# CPU.net
KiCad netlist of a schematic drawn in Altium Designer
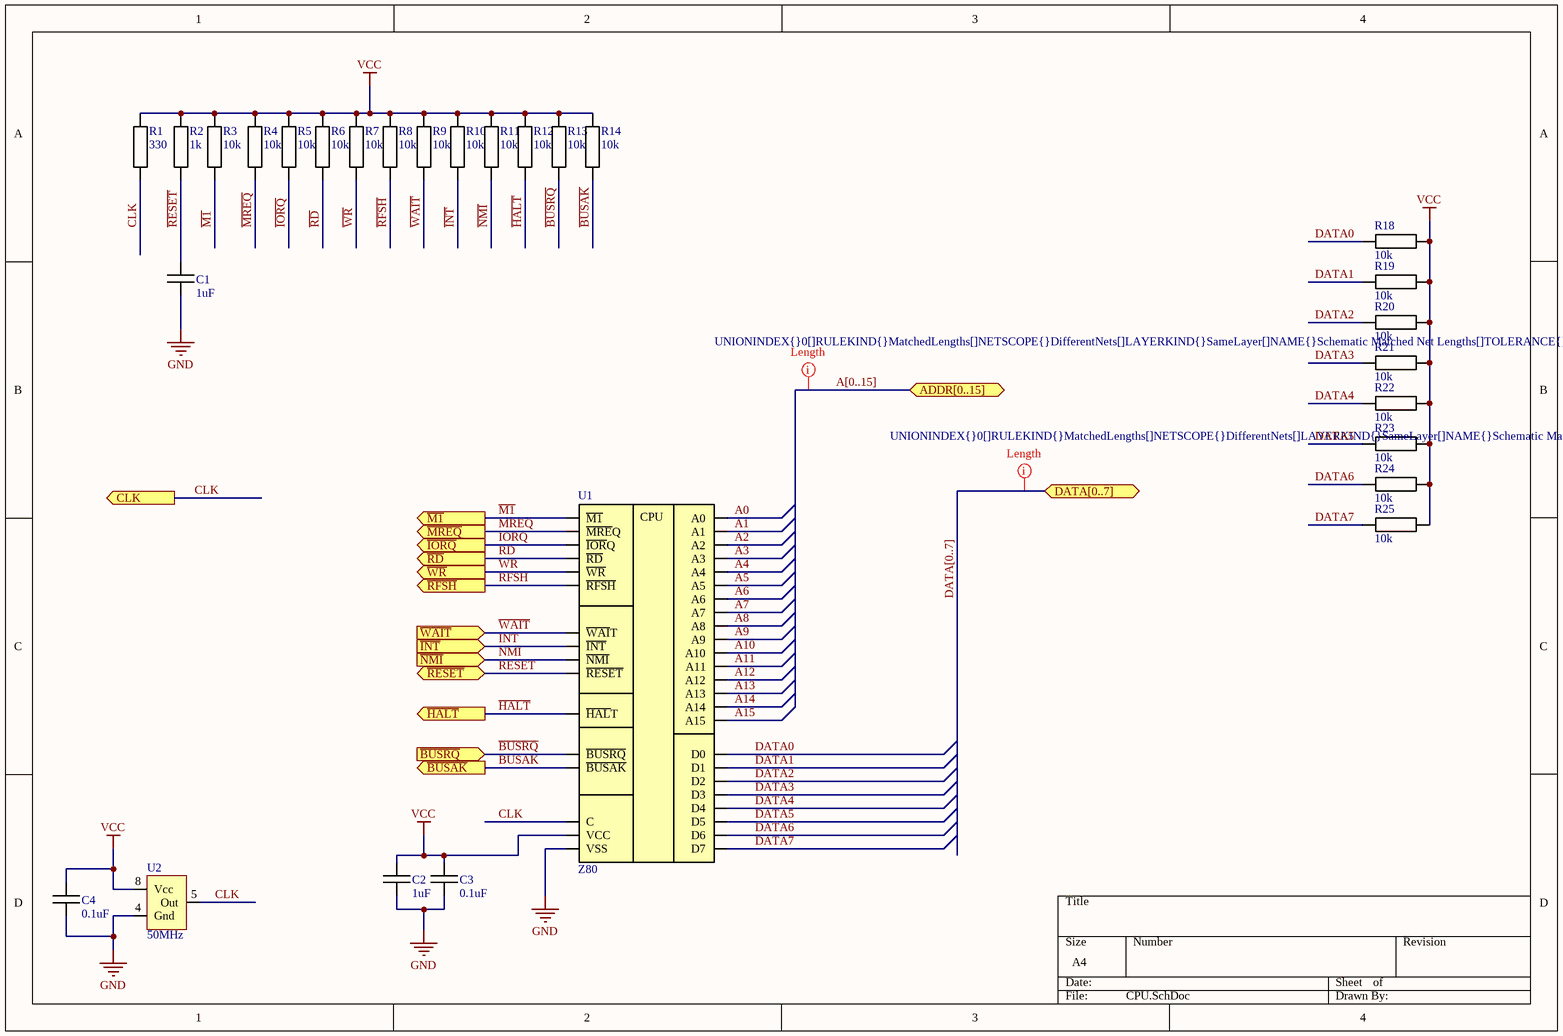
[diagram p0: CPU.SchDoc]

(export (version "E")
  (design (tool "Eeschema 10.0.6"))
  (components
    (comp (ref "C1") (value "1uF") (footprint "SMD 0603") (libsource (lib "Maks_lib") (part "Capasitor")))
    (comp (ref "C2") (value "1uF") (footprint "SMD 0603") (libsource (lib "Maks_lib") (part "Capasitor")))
    (comp (ref "C3") (value "0.1uF") (footprint "SMD 0603") (libsource (lib "Maks_lib") (part "Capasitor")))
    (comp (ref "C4") (value "0.1uF") (footprint "SMD 0603") (libsource (lib "Maks_lib") (part "Capasitor")))
    (comp (ref "R1") (value "330") (footprint "SMD 0603") (libsource (lib "Maks_lib") (part "Resistor")))
    (comp (ref "R2") (value "1k") (footprint "SMD 0603") (libsource (lib "Maks_lib") (part "Resistor")))
    (comp (ref "R3") (value "10k") (footprint "SMD 0603") (libsource (lib "Maks_lib") (part "Resistor")))
    (comp (ref "R4") (value "10k") (footprint "SMD 0603") (libsource (lib "Maks_lib") (part "Resistor")))
    (comp (ref "R5") (value "10k") (footprint "SMD 0603") (libsource (lib "Maks_lib") (part "Resistor")))
    (comp (ref "R6") (value "10k") (footprint "SMD 0603") (libsource (lib "Maks_lib") (part "Resistor")))
    (comp (ref "R7") (value "10k") (footprint "SMD 0603") (libsource (lib "Maks_lib") (part "Resistor")))
    (comp (ref "R8") (value "10k") (footprint "SMD 0603") (libsource (lib "Maks_lib") (part "Resistor")))
    (comp (ref "R9") (value "10k") (footprint "SMD 0603") (libsource (lib "Maks_lib") (part "Resistor")))
    (comp (ref "R10") (value "10k") (footprint "SMD 0603") (libsource (lib "Maks_lib") (part "Resistor")))
    (comp (ref "R11") (value "10k") (footprint "SMD 0603") (libsource (lib "Maks_lib") (part "Resistor")))
    (comp (ref "R12") (value "10k") (footprint "SMD 0603") (libsource (lib "Maks_lib") (part "Resistor")))
    (comp (ref "R13") (value "10k") (footprint "SMD 0603") (libsource (lib "Maks_lib") (part "Resistor")))
    (comp (ref "R14") (value "10k") (footprint "SMD 0603") (libsource (lib "Maks_lib") (part "Resistor")))
    (comp (ref "R18") (value "10k") (footprint "SMD 0603") (libsource (lib "Maks_lib") (part "Resistor")))
    (comp (ref "R19") (value "10k") (footprint "SMD 0603") (libsource (lib "Maks_lib") (part "Resistor")))
    (comp (ref "R20") (value "10k") (footprint "SMD 0603") (libsource (lib "Maks_lib") (part "Resistor")))
    (comp (ref "R21") (value "10k") (footprint "SMD 0603") (libsource (lib "Maks_lib") (part "Resistor")))
    (comp (ref "R22") (value "10k") (footprint "SMD 0603") (libsource (lib "Maks_lib") (part "Resistor")))
    (comp (ref "R23") (value "10k") (footprint "SMD 0603") (libsource (lib "Maks_lib") (part "Resistor")))
    (comp (ref "R24") (value "10k") (footprint "SMD 0603") (libsource (lib "Maks_lib") (part "Resistor")))
    (comp (ref "R25") (value "10k") (footprint "SMD 0603") (libsource (lib "Maks_lib") (part "Resistor")))
    (comp (ref "U1")
      (value "Z80")
      (footprint "Z80")
      (description "Zilog CPU")
      (libsource (lib "Maks_lib") (part "Z80"))
    )
    (comp (ref "U2") (value "50MHz") (footprint "XTALL GEN") (libsource (lib "Maks_lib") (part "XTALL GEN")))
  )
  (nets
    (net (code "1") (name "/A0") (class "Default")
      (node (ref "U1") (pin "30") (pinfunction "A0_30") (pintype "passive"))
    )
    (net (code "2") (name "/A1") (class "Default")
      (node (ref "U1") (pin "31") (pinfunction "A1_31") (pintype "passive"))
    )
    (net (code "3") (name "/A2") (class "Default")
      (node (ref "U1") (pin "32") (pinfunction "A2_32") (pintype "passive"))
    )
    (net (code "4") (name "/A3") (class "Default")
      (node (ref "U1") (pin "33") (pinfunction "A3_33") (pintype "passive"))
    )
    (net (code "5") (name "/A4") (class "Default")
      (node (ref "U1") (pin "34") (pinfunction "A4_34") (pintype "passive"))
    )
    (net (code "6") (name "/A5") (class "Default")
      (node (ref "U1") (pin "35") (pinfunction "A5_35") (pintype "passive"))
    )
    (net (code "7") (name "/A6") (class "Default")
      (node (ref "U1") (pin "36") (pinfunction "A6_36") (pintype "passive"))
    )
    (net (code "8") (name "/A7") (class "Default")
      (node (ref "U1") (pin "37") (pinfunction "A7_37") (pintype "passive"))
    )
    (net (code "9") (name "/A8") (class "Default")
      (node (ref "U1") (pin "38") (pinfunction "A8_38") (pintype "passive"))
    )
    (net (code "10") (name "/A9") (class "Default")
      (node (ref "U1") (pin "39") (pinfunction "A9_39") (pintype "passive"))
    )
    (net (code "11") (name "/A10") (class "Default")
      (node (ref "U1") (pin "40") (pinfunction "A10_40") (pintype "passive"))
    )
    (net (code "12") (name "/A11") (class "Default")
      (node (ref "U1") (pin "1") (pinfunction "A11_1") (pintype "passive"))
    )
    (net (code "13") (name "/A12") (class "Default")
      (node (ref "U1") (pin "2") (pinfunction "A12_2") (pintype "passive"))
    )
    (net (code "14") (name "/A13") (class "Default")
      (node (ref "U1") (pin "3") (pinfunction "A13_3") (pintype "passive"))
    )
    (net (code "15") (name "/A14") (class "Default")
      (node (ref "U1") (pin "4") (pinfunction "A14_4") (pintype "passive"))
    )
    (net (code "16") (name "/A15") (class "Default")
      (node (ref "U1") (pin "5") (pinfunction "A15_5") (pintype "passive"))
    )
    (net (code "18") (name "/BUSAK") (class "Default")
      (node (ref "R14") (pin "1") (pinfunction "1_1") (pintype "passive"))
      (node (ref "U1") (pin "23") (pinfunction "~{BUSAK}_23") (pintype "passive"))
    )
    (net (code "19") (name "/BUSRQ") (class "Default")
      (node (ref "R13") (pin "1") (pinfunction "1_1") (pintype "passive"))
      (node (ref "U1") (pin "25") (pinfunction "~{BUSRQ}_25") (pintype "passive"))
    )
    (net (code "20") (name "/CLK") (class "Default")
      (node (ref "R1") (pin "1") (pinfunction "1_1") (pintype "passive"))
      (node (ref "U1") (pin "6") (pinfunction "C_6") (pintype "passive"))
      (node (ref "U2") (pin "5") (pinfunction "Out_5") (pintype "passive"))
    )
    (net (code "21") (name "/DATA0") (class "Default")
      (node (ref "R18") (pin "1") (pinfunction "1_1") (pintype "passive"))
      (node (ref "U1") (pin "14") (pinfunction "D0_14") (pintype "passive"))
    )
    (net (code "22") (name "/DATA1") (class "Default")
      (node (ref "R19") (pin "1") (pinfunction "1_1") (pintype "passive"))
      (node (ref "U1") (pin "15") (pinfunction "D1_15") (pintype "passive"))
    )
    (net (code "23") (name "/DATA2") (class "Default")
      (node (ref "R20") (pin "1") (pinfunction "1_1") (pintype "passive"))
      (node (ref "U1") (pin "12") (pinfunction "D2_12") (pintype "passive"))
    )
    (net (code "24") (name "/DATA3") (class "Default")
      (node (ref "R21") (pin "1") (pinfunction "1_1") (pintype "passive"))
      (node (ref "U1") (pin "8") (pinfunction "D3_8") (pintype "passive"))
    )
    (net (code "25") (name "/DATA4") (class "Default")
      (node (ref "R22") (pin "1") (pinfunction "1_1") (pintype "passive"))
      (node (ref "U1") (pin "7") (pinfunction "D4_7") (pintype "passive"))
    )
    (net (code "26") (name "/DATA5") (class "Default")
      (node (ref "R23") (pin "1") (pinfunction "1_1") (pintype "passive"))
      (node (ref "U1") (pin "9") (pinfunction "D5_9") (pintype "passive"))
    )
    (net (code "27") (name "/DATA6") (class "Default")
      (node (ref "R24") (pin "1") (pinfunction "1_1") (pintype "passive"))
      (node (ref "U1") (pin "10") (pinfunction "D6_10") (pintype "passive"))
    )
    (net (code "28") (name "/DATA7") (class "Default")
      (node (ref "R25") (pin "1") (pinfunction "1_1") (pintype "passive"))
      (node (ref "U1") (pin "13") (pinfunction "D7_13") (pintype "passive"))
    )
    (net (code "30") (name "/HALT") (class "Default")
      (node (ref "R12") (pin "1") (pinfunction "1_1") (pintype "passive"))
      (node (ref "U1") (pin "18") (pinfunction "~{HAL}T_18") (pintype "passive"))
    )
    (net (code "31") (name "/INT") (class "Default")
      (node (ref "R10") (pin "1") (pinfunction "1_1") (pintype "passive"))
      (node (ref "U1") (pin "16") (pinfunction "~{INT}_16") (pintype "passive"))
    )
    (net (code "32") (name "/IORQ") (class "Default")
      (node (ref "R5") (pin "1") (pinfunction "1_1") (pintype "passive"))
      (node (ref "U1") (pin "20") (pinfunction "~{IOR}Q_20") (pintype "passive"))
    )
    (net (code "33") (name "/M1") (class "Default")
      (node (ref "R3") (pin "1") (pinfunction "1_1") (pintype "passive"))
      (node (ref "U1") (pin "27") (pinfunction "~{M1}_27") (pintype "passive"))
    )
    (net (code "34") (name "/MREQ") (class "Default")
      (node (ref "R4") (pin "1") (pinfunction "1_1") (pintype "passive"))
      (node (ref "U1") (pin "19") (pinfunction "~{MRE}Q_19") (pintype "passive"))
    )
    (net (code "35") (name "/NMI") (class "Default")
      (node (ref "R11") (pin "1") (pinfunction "1_1") (pintype "passive"))
      (node (ref "U1") (pin "17") (pinfunction "~{NMI}_17") (pintype "passive"))
    )
    (net (code "36") (name "/RD") (class "Default")
      (node (ref "R6") (pin "1") (pinfunction "1_1") (pintype "passive"))
      (node (ref "U1") (pin "21") (pinfunction "~{RD}_21") (pintype "passive"))
    )
    (net (code "37") (name "/RESET") (class "Default")
      (node (ref "C1") (pin "2") (pinfunction "2_2") (pintype "passive"))
      (node (ref "R2") (pin "1") (pinfunction "1_1") (pintype "passive"))
      (node (ref "U1") (pin "26") (pinfunction "~{RESET}_26") (pintype "passive"))
    )
    (net (code "38") (name "/RFSH") (class "Default")
      (node (ref "R8") (pin "1") (pinfunction "1_1") (pintype "passive"))
      (node (ref "U1") (pin "28") (pinfunction "~{RFSH}_28") (pintype "passive"))
    )
    (net (code "39") (name "/WAIT") (class "Default")
      (node (ref "R9") (pin "1") (pinfunction "1_1") (pintype "passive"))
      (node (ref "U1") (pin "24") (pinfunction "~{WAI}T_24") (pintype "passive"))
    )
    (net (code "40") (name "/WR") (class "Default")
      (node (ref "R7") (pin "1") (pinfunction "1_1") (pintype "passive"))
      (node (ref "U1") (pin "22") (pinfunction "~{WR}_22") (pintype "passive"))
    )
    (net (code "41") (name "GND") (class "Default")
      (node (ref "C1") (pin "1") (pinfunction "1_1") (pintype "passive"))
      (node (ref "C2") (pin "1") (pinfunction "1_1") (pintype "passive"))
      (node (ref "C3") (pin "1") (pinfunction "1_1") (pintype "passive"))
      (node (ref "C4") (pin "1") (pinfunction "1_1") (pintype "passive"))
      (node (ref "U1") (pin "29") (pinfunction "VSS_29") (pintype "passive"))
      (node (ref "U2") (pin "4") (pinfunction "Gnd_4") (pintype "passive"))
    )
    (net (code "42") (name "VCC") (class "Default")
      (node (ref "C2") (pin "2") (pinfunction "2_2") (pintype "passive"))
      (node (ref "C3") (pin "2") (pinfunction "2_2") (pintype "passive"))
      (node (ref "C4") (pin "2") (pinfunction "2_2") (pintype "passive"))
      (node (ref "R1") (pin "2") (pinfunction "2_2") (pintype "passive"))
      (node (ref "R10") (pin "2") (pinfunction "2_2") (pintype "passive"))
      (node (ref "R11") (pin "2") (pinfunction "2_2") (pintype "passive"))
      (node (ref "R12") (pin "2") (pinfunction "2_2") (pintype "passive"))
      (node (ref "R13") (pin "2") (pinfunction "2_2") (pintype "passive"))
      (node (ref "R14") (pin "2") (pinfunction "2_2") (pintype "passive"))
      (node (ref "R18") (pin "2") (pinfunction "2_2") (pintype "passive"))
      (node (ref "R19") (pin "2") (pinfunction "2_2") (pintype "passive"))
      (node (ref "R2") (pin "2") (pinfunction "2_2") (pintype "passive"))
      (node (ref "R20") (pin "2") (pinfunction "2_2") (pintype "passive"))
      (node (ref "R21") (pin "2") (pinfunction "2_2") (pintype "passive"))
      (node (ref "R22") (pin "2") (pinfunction "2_2") (pintype "passive"))
      (node (ref "R23") (pin "2") (pinfunction "2_2") (pintype "passive"))
      (node (ref "R24") (pin "2") (pinfunction "2_2") (pintype "passive"))
      (node (ref "R25") (pin "2") (pinfunction "2_2") (pintype "passive"))
      (node (ref "R3") (pin "2") (pinfunction "2_2") (pintype "passive"))
      (node (ref "R4") (pin "2") (pinfunction "2_2") (pintype "passive"))
      (node (ref "R5") (pin "2") (pinfunction "2_2") (pintype "passive"))
      (node (ref "R6") (pin "2") (pinfunction "2_2") (pintype "passive"))
      (node (ref "R7") (pin "2") (pinfunction "2_2") (pintype "passive"))
      (node (ref "R8") (pin "2") (pinfunction "2_2") (pintype "passive"))
      (node (ref "R9") (pin "2") (pinfunction "2_2") (pintype "passive"))
      (node (ref "U1") (pin "11") (pinfunction "VCC_11") (pintype "passive"))
      (node (ref "U2") (pin "8") (pinfunction "Vcc_8") (pintype "passive"))
    )
  )
)
